# System_Schematic.net
KiCad netlist of a schematic drawn in EAGLE
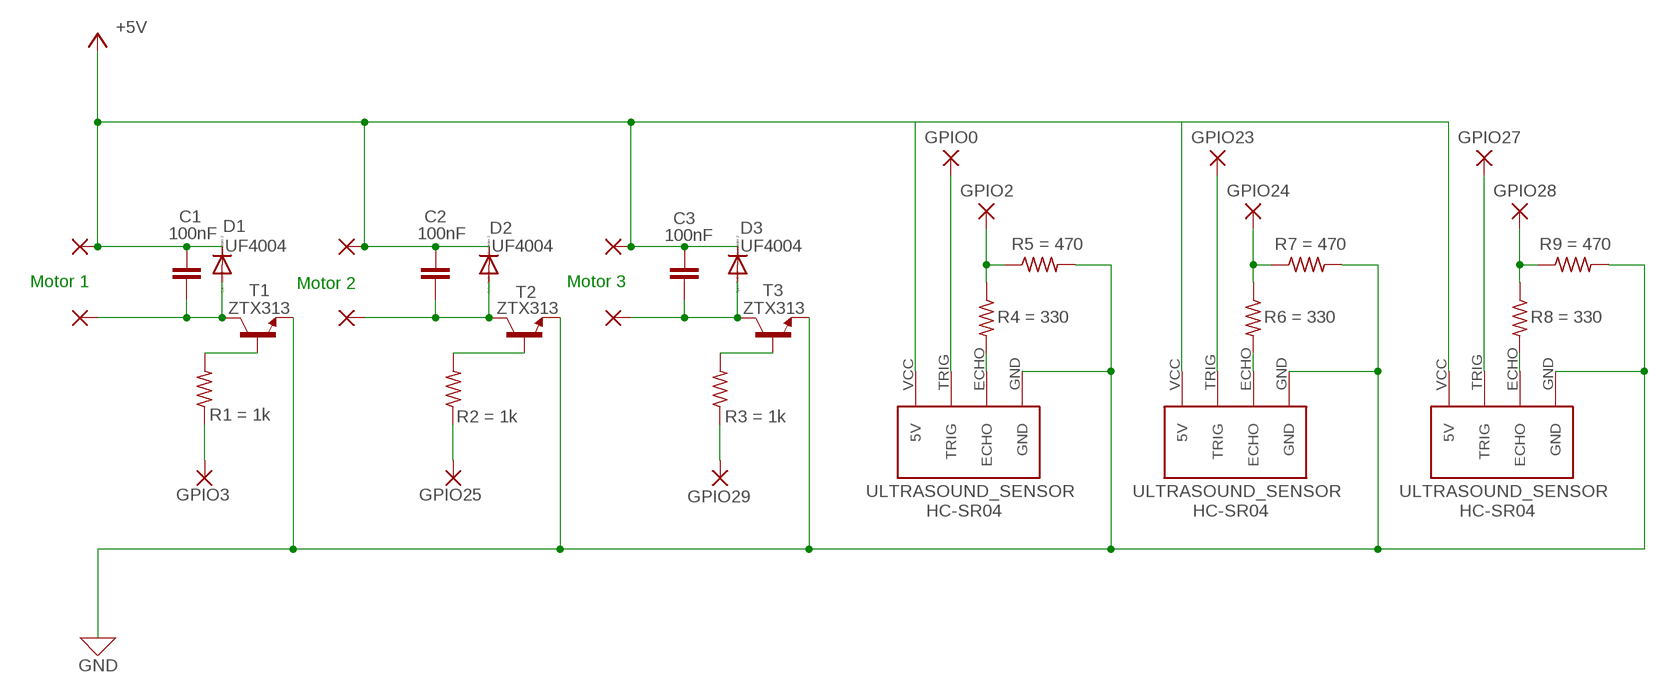
[diagram p0: schematic, sheet 1]

(export (version "E")
  (design (tool "Eeschema 10.0.6"))
  (components
    (comp (ref "C1")
      (value "C15/6")
      (footprint "eagle-import:C15B6")
      (fields (field (name "CAPPYU") "100nF"))
      (libsource (lib "eagle-import") (part "C15/6"))
    )
    (comp (ref "C2")
      (value "C15/6")
      (footprint "eagle-import:C15B6")
      (fields (field (name "CAPPY") "100nF"))
      (libsource (lib "eagle-import") (part "C15/6"))
    )
    (comp (ref "C3")
      (value "C15/6")
      (footprint "eagle-import:C15B6")
      (fields (field (name "CAPPY") "100nF"))
      (libsource (lib "eagle-import") (part "C15/6"))
    )
    (comp (ref "D1")
      (value "BA243A")
      (footprint "eagle-import:DO35-10")
      (libsource (lib "eagle-import") (part "BA243A"))
    )
    (comp (ref "D2")
      (value "BA243A")
      (footprint "eagle-import:DO35-10")
      (libsource (lib "eagle-import") (part "BA243A"))
    )
    (comp (ref "D3")
      (value "BA243A")
      (footprint "eagle-import:DO35-10")
      (libsource (lib "eagle-import") (part "BA243A"))
    )
    (comp (ref "J_ULTRASONIC_1")
      (value "HC-SR04")
      (footprint "eagle-import:HC-SR04_FOOTPRINT")
      (libsource (lib "eagle-import") (part "HC-SR04"))
    )
    (comp (ref "J_ULTRASONIC_2")
      (value "HC-SR04")
      (footprint "eagle-import:HC-SR04_FOOTPRINT")
      (libsource (lib "eagle-import") (part "HC-SR04"))
    )
    (comp (ref "J_ULTRASONIC_3")
      (value "HC-SR04")
      (footprint "eagle-import:HC-SR04_FOOTPRINT")
      (libsource (lib "eagle-import") (part "HC-SR04"))
    )
    (comp (ref "PAD1")
      (value "3,81/1,4")
      (footprint "eagle-import:3,81_1,4")
      (libsource (lib "eagle-import") (part "3,81/1,4"))
    )
    (comp (ref "PAD2")
      (value "3,81/1,4")
      (footprint "eagle-import:3,81_1,4")
      (libsource (lib "eagle-import") (part "3,81/1,4"))
    )
    (comp (ref "PAD3")
      (value "3,81/1,4")
      (footprint "eagle-import:3,81_1,4")
      (libsource (lib "eagle-import") (part "3,81/1,4"))
    )
    (comp (ref "PAD4")
      (value "3,81/1,4")
      (footprint "eagle-import:3,81_1,4")
      (libsource (lib "eagle-import") (part "3,81/1,4"))
    )
    (comp (ref "PAD5")
      (value "3,81/1,4")
      (footprint "eagle-import:3,81_1,4")
      (libsource (lib "eagle-import") (part "3,81/1,4"))
    )
    (comp (ref "PAD6")
      (value "3,81/1,4")
      (footprint "eagle-import:3,81_1,4")
      (libsource (lib "eagle-import") (part "3,81/1,4"))
    )
    (comp (ref "PAD7")
      (value "3,81/1,4")
      (footprint "eagle-import:3,81_1,4")
      (libsource (lib "eagle-import") (part "3,81/1,4"))
    )
    (comp (ref "PAD8")
      (value "3,81/1,4")
      (footprint "eagle-import:3,81_1,4")
      (libsource (lib "eagle-import") (part "3,81/1,4"))
    )
    (comp (ref "PAD9")
      (value "3,81/1,4")
      (footprint "eagle-import:3,81_1,4")
      (libsource (lib "eagle-import") (part "3,81/1,4"))
    )
    (comp (ref "PAD10")
      (value "3,81/1,4")
      (footprint "eagle-import:3,81_1,4")
      (libsource (lib "eagle-import") (part "3,81/1,4"))
    )
    (comp (ref "PAD11")
      (value "3,81/1,4")
      (footprint "eagle-import:3,81_1,4")
      (libsource (lib "eagle-import") (part "3,81/1,4"))
    )
    (comp (ref "PAD12")
      (value "3,81/1,4")
      (footprint "eagle-import:3,81_1,4")
      (libsource (lib "eagle-import") (part "3,81/1,4"))
    )
    (comp (ref "PAD13")
      (value "3,81/1,4")
      (footprint "eagle-import:3,81_1,4")
      (libsource (lib "eagle-import") (part "3,81/1,4"))
    )
    (comp (ref "PAD14")
      (value "3,81/1,4")
      (footprint "eagle-import:3,81_1,4")
      (libsource (lib "eagle-import") (part "3,81/1,4"))
    )
    (comp (ref "PAD15")
      (value "3,81/1,4")
      (footprint "eagle-import:3,81_1,4")
      (libsource (lib "eagle-import") (part "3,81/1,4"))
    )
    (comp (ref "R1")
      (value "R-US_0207/15")
      (footprint "eagle-import:0207_15")
      (fields (field (name "R1") "1k") (field (name "SPICEPREFIX") "1k"))
      (libsource (lib "eagle-import") (part "R-US_0207/15"))
    )
    (comp (ref "R2")
      (value "R-US_0207/15")
      (footprint "eagle-import:0207_15")
      (fields (field (name "R2") "1k") (field (name "SPICEPREFIX") "1k"))
      (libsource (lib "eagle-import") (part "R-US_0207/15"))
    )
    (comp (ref "R3")
      (value "R-US_0207/15")
      (footprint "eagle-import:0207_15")
      (fields (field (name "R3") "1k") (field (name "SPICEPREFIX") "1k"))
      (libsource (lib "eagle-import") (part "R-US_0207/15"))
    )
    (comp (ref "R4")
      (value "R-US_0207/15")
      (footprint "eagle-import:0207_15")
      (fields (field (name "R6") "330") (field (name "SPICEPREFIX") "1k"))
      (libsource (lib "eagle-import") (part "R-US_0207/15"))
    )
    (comp (ref "R5")
      (value "R-US_0207/15")
      (footprint "eagle-import:0207_15")
      (fields (field (name "R7") "470") (field (name "SPICEPREFIX") "1k"))
      (libsource (lib "eagle-import") (part "R-US_0207/15"))
    )
    (comp (ref "R6")
      (value "R-US_0207/15")
      (footprint "eagle-import:0207_15")
      (fields (field (name "R8") "330") (field (name "SPICEPREFIX") "1k"))
      (libsource (lib "eagle-import") (part "R-US_0207/15"))
    )
    (comp (ref "R7")
      (value "R-US_0207/15")
      (footprint "eagle-import:0207_15")
      (fields (field (name "R9") "470") (field (name "SPICEPREFIX") "1k"))
      (libsource (lib "eagle-import") (part "R-US_0207/15"))
    )
    (comp (ref "R8")
      (value "R-US_0207/15")
      (footprint "eagle-import:0207_15")
      (fields (field (name "R4") "330") (field (name "SPICEPREFIX") "1k"))
      (libsource (lib "eagle-import") (part "R-US_0207/15"))
    )
    (comp (ref "R9")
      (value "R-US_0207/15")
      (footprint "eagle-import:0207_15")
      (fields (field (name "R5") "470") (field (name "SPICEPREFIX") "1k"))
      (libsource (lib "eagle-import") (part "R-US_0207/15"))
    )
    (comp (ref "T1")
      (value "2N706")
      (footprint "eagle-import:TO18")
      (libsource (lib "eagle-import") (part "2N706"))
    )
    (comp (ref "T2")
      (value "2N706")
      (footprint "eagle-import:TO18")
      (libsource (lib "eagle-import") (part "2N706"))
    )
    (comp (ref "T3")
      (value "2N706")
      (footprint "eagle-import:TO18")
      (libsource (lib "eagle-import") (part "2N706"))
    )
  )
  (nets
    (net (code "1") (name "+5V") (class "Default")
      (node (ref "C1") (pin "1") (pinfunction "1_1") (pintype "passive"))
      (node (ref "C2") (pin "1") (pinfunction "1_1") (pintype "passive"))
      (node (ref "C3") (pin "1") (pinfunction "1_1") (pintype "passive"))
      (node (ref "D1") (pin "C") (pinfunction "C_C") (pintype "passive"))
      (node (ref "D2") (pin "C") (pinfunction "C_C") (pintype "passive"))
      (node (ref "D3") (pin "C") (pinfunction "C_C") (pintype "passive"))
      (node (ref "J_ULTRASONIC_1") (pin "VCC") (pinfunction "5V_VCC") (pintype "bidirectional"))
      (node (ref "PAD5") (pin "1") (pinfunction "P_1") (pintype "passive"))
      (node (ref "PAD6") (pin "1") (pinfunction "P_1") (pintype "passive"))
      (node (ref "PAD9") (pin "1") (pinfunction "P_1") (pintype "passive"))
    )
    (net (code "2") (name "GND") (class "Default")
      (node (ref "J_ULTRASONIC_1") (pin "GND") (pinfunction "GND_GND") (pintype "bidirectional"))
      (node (ref "J_ULTRASONIC_2") (pin "GND") (pinfunction "GND_GND") (pintype "bidirectional"))
      (node (ref "J_ULTRASONIC_3") (pin "GND") (pinfunction "GND_GND") (pintype "bidirectional"))
      (node (ref "R5") (pin "2") (pinfunction "2_2") (pintype "passive"))
      (node (ref "R7") (pin "2") (pinfunction "2_2") (pintype "passive"))
      (node (ref "R9") (pin "2") (pinfunction "2_2") (pintype "passive"))
      (node (ref "T1") (pin "1") (pinfunction "E_1") (pintype "passive"))
      (node (ref "T2") (pin "1") (pinfunction "E_1") (pintype "passive"))
      (node (ref "T3") (pin "1") (pinfunction "E_1") (pintype "passive"))
    )
    (net (code "3") (name "Net-(J_ULTRASONIC_1-PadECHO)") (class "Default")
      (node (ref "J_ULTRASONIC_1") (pin "ECHO") (pinfunction "ECHO_ECHO") (pintype "bidirectional"))
      (node (ref "R8") (pin "2") (pinfunction "2_2") (pintype "passive"))
    )
    (net (code "4") (name "Net-(J_ULTRASONIC_2-PadECHO)") (class "Default")
      (node (ref "J_ULTRASONIC_2") (pin "ECHO") (pinfunction "ECHO_ECHO") (pintype "bidirectional"))
      (node (ref "R4") (pin "2") (pinfunction "2_2") (pintype "passive"))
    )
    (net (code "5") (name "Net-(J_ULTRASONIC_3-PadECHO)") (class "Default")
      (node (ref "J_ULTRASONIC_3") (pin "ECHO") (pinfunction "ECHO_ECHO") (pintype "bidirectional"))
      (node (ref "R6") (pin "2") (pinfunction "2_2") (pintype "passive"))
    )
    (net (code "6") (name "Net-(PAD1-P)") (class "Default")
      (node (ref "PAD1") (pin "1") (pinfunction "P_1") (pintype "passive"))
      (node (ref "R1") (pin "1") (pinfunction "1_1") (pintype "passive"))
    )
    (net (code "7") (name "Net-(PAD2-P)") (class "Default")
      (node (ref "PAD2") (pin "1") (pinfunction "P_1") (pintype "passive"))
      (node (ref "R2") (pin "1") (pinfunction "1_1") (pintype "passive"))
    )
    (net (code "8") (name "Net-(PAD3-P)") (class "Default")
      (node (ref "PAD3") (pin "1") (pinfunction "P_1") (pintype "passive"))
      (node (ref "R3") (pin "1") (pinfunction "1_1") (pintype "passive"))
    )
    (net (code "9") (name "Net-(PAD4-P)") (class "Default")
      (node (ref "C1") (pin "2") (pinfunction "2_2") (pintype "passive"))
      (node (ref "D1") (pin "A") (pinfunction "A_A") (pintype "passive"))
      (node (ref "PAD4") (pin "1") (pinfunction "P_1") (pintype "passive"))
      (node (ref "T1") (pin "3") (pinfunction "C_3") (pintype "passive"))
    )
    (net (code "10") (name "Net-(PAD7-P)") (class "Default")
      (node (ref "C2") (pin "2") (pinfunction "2_2") (pintype "passive"))
      (node (ref "D2") (pin "A") (pinfunction "A_A") (pintype "passive"))
      (node (ref "PAD7") (pin "1") (pinfunction "P_1") (pintype "passive"))
      (node (ref "T2") (pin "3") (pinfunction "C_3") (pintype "passive"))
    )
    (net (code "11") (name "Net-(PAD8-P)") (class "Default")
      (node (ref "C3") (pin "2") (pinfunction "2_2") (pintype "passive"))
      (node (ref "D3") (pin "A") (pinfunction "A_A") (pintype "passive"))
      (node (ref "PAD8") (pin "1") (pinfunction "P_1") (pintype "passive"))
      (node (ref "T3") (pin "3") (pinfunction "C_3") (pintype "passive"))
    )
    (net (code "12") (name "Net-(PAD10-P)") (class "Default")
      (node (ref "J_ULTRASONIC_2") (pin "TRIG") (pinfunction "TRIG_TRIG") (pintype "bidirectional"))
      (node (ref "PAD10") (pin "1") (pinfunction "P_1") (pintype "passive"))
    )
    (net (code "13") (name "Net-(PAD11-P)") (class "Default")
      (node (ref "J_ULTRASONIC_1") (pin "TRIG") (pinfunction "TRIG_TRIG") (pintype "bidirectional"))
      (node (ref "PAD11") (pin "1") (pinfunction "P_1") (pintype "passive"))
    )
    (net (code "14") (name "Net-(PAD12-P)") (class "Default")
      (node (ref "PAD12") (pin "1") (pinfunction "P_1") (pintype "passive"))
      (node (ref "R4") (pin "1") (pinfunction "1_1") (pintype "passive"))
      (node (ref "R5") (pin "1") (pinfunction "1_1") (pintype "passive"))
    )
    (net (code "15") (name "Net-(PAD13-P)") (class "Default")
      (node (ref "J_ULTRASONIC_3") (pin "TRIG") (pinfunction "TRIG_TRIG") (pintype "bidirectional"))
      (node (ref "PAD13") (pin "1") (pinfunction "P_1") (pintype "passive"))
    )
    (net (code "16") (name "Net-(PAD14-P)") (class "Default")
      (node (ref "PAD14") (pin "1") (pinfunction "P_1") (pintype "passive"))
      (node (ref "R6") (pin "1") (pinfunction "1_1") (pintype "passive"))
      (node (ref "R7") (pin "1") (pinfunction "1_1") (pintype "passive"))
    )
    (net (code "17") (name "Net-(PAD15-P)") (class "Default")
      (node (ref "PAD15") (pin "1") (pinfunction "P_1") (pintype "passive"))
      (node (ref "R8") (pin "1") (pinfunction "1_1") (pintype "passive"))
      (node (ref "R9") (pin "1") (pinfunction "1_1") (pintype "passive"))
    )
    (net (code "18") (name "Net-(T1-B)") (class "Default")
      (node (ref "R1") (pin "2") (pinfunction "2_2") (pintype "passive"))
      (node (ref "T1") (pin "2") (pinfunction "B_2") (pintype "passive"))
    )
    (net (code "19") (name "Net-(T2-B)") (class "Default")
      (node (ref "R2") (pin "2") (pinfunction "2_2") (pintype "passive"))
      (node (ref "T2") (pin "2") (pinfunction "B_2") (pintype "passive"))
    )
    (net (code "20") (name "Net-(T3-B)") (class "Default")
      (node (ref "R3") (pin "2") (pinfunction "2_2") (pintype "passive"))
      (node (ref "T3") (pin "2") (pinfunction "B_2") (pintype "passive"))
    )
    (net (code "21") (name "unconnected-(J_ULTRASONIC_2-5V-PadVCC)") (class "Default")
      (node (ref "J_ULTRASONIC_2") (pin "VCC") (pinfunction "5V_VCC") (pintype "bidirectional"))
    )
    (net (code "22") (name "unconnected-(J_ULTRASONIC_3-5V-PadVCC)") (class "Default")
      (node (ref "J_ULTRASONIC_3") (pin "VCC") (pinfunction "5V_VCC") (pintype "bidirectional"))
    )
  )
)
